# RP2350A_DEV_Template.net
KiCad netlist of a schematic drawn in EAGLE
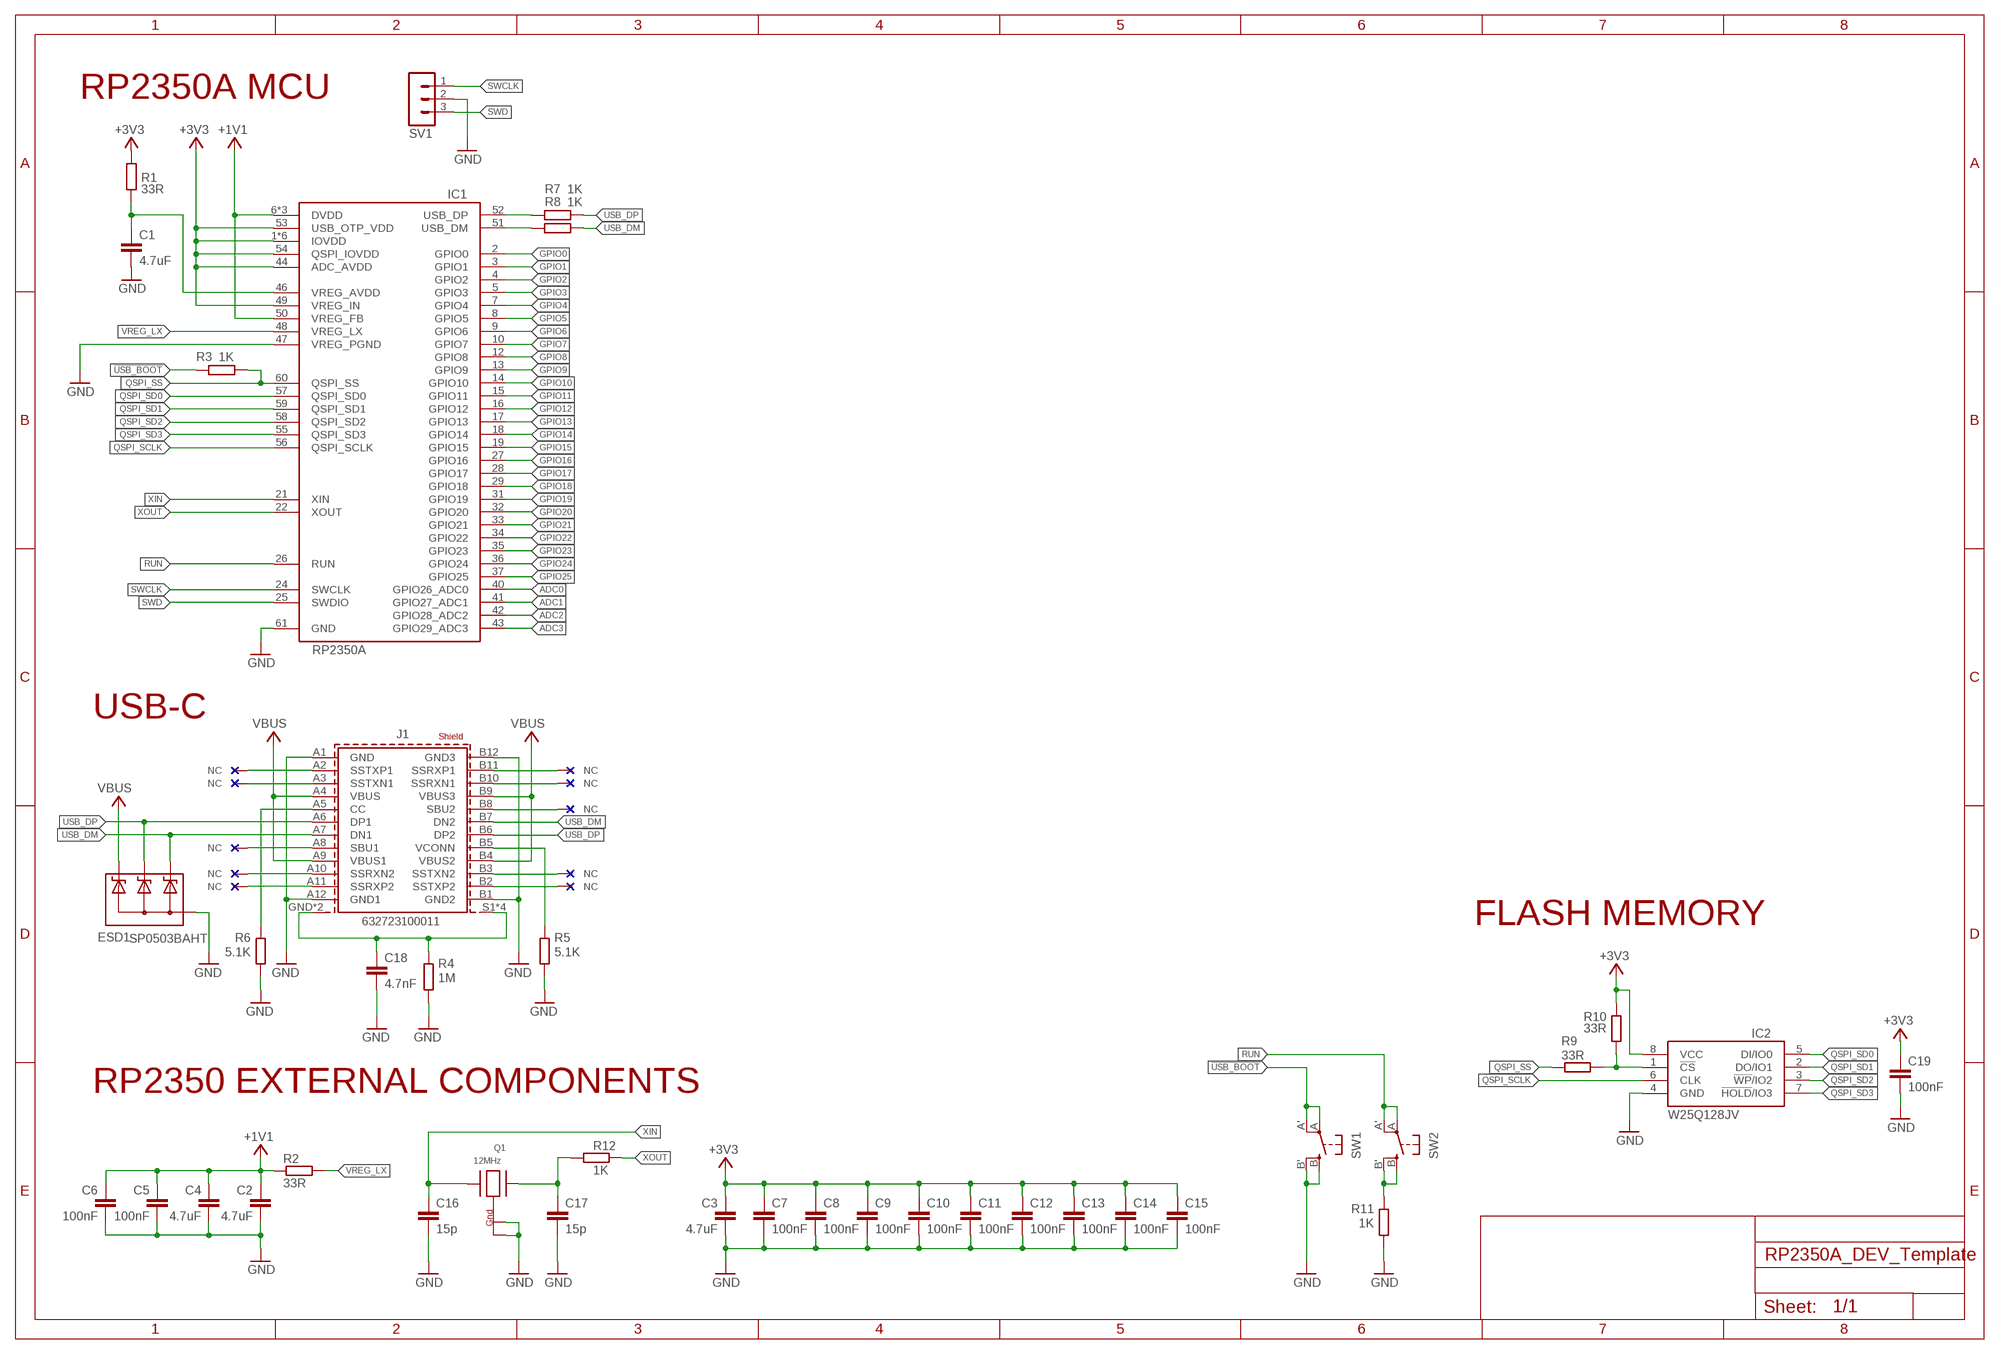
[diagram p0: schematic, sheet 1]

(export (version "E")
  (design (tool "Eeschema 10.0.6"))
  (components
    (comp (ref "C1")
      (value "4.7uF")
      (footprint "eagle-import:C0402K")
      (libsource (lib "eagle-import") (part "C-EUC0402K"))
    )
    (comp (ref "C2")
      (value "4.7uF")
      (footprint "eagle-import:C0402K")
      (libsource (lib "eagle-import") (part "C-EUC0402K"))
    )
    (comp (ref "C3")
      (value "4.7uF")
      (footprint "eagle-import:C0402K")
      (libsource (lib "eagle-import") (part "C-EUC0402K"))
    )
    (comp (ref "C4")
      (value "4.7uF")
      (footprint "eagle-import:C0402K")
      (libsource (lib "eagle-import") (part "C-EUC0402K"))
    )
    (comp (ref "C5")
      (value "100nF")
      (footprint "eagle-import:C0402K")
      (libsource (lib "eagle-import") (part "C-EUC0402K"))
    )
    (comp (ref "C6")
      (value "100nF")
      (footprint "eagle-import:C0402K")
      (libsource (lib "eagle-import") (part "C-EUC0402K"))
    )
    (comp (ref "C7")
      (value "100nF")
      (footprint "eagle-import:C0402K")
      (libsource (lib "eagle-import") (part "C-EUC0402K"))
    )
    (comp (ref "C8")
      (value "100nF")
      (footprint "eagle-import:C0402K")
      (libsource (lib "eagle-import") (part "C-EUC0402K"))
    )
    (comp (ref "C9")
      (value "100nF")
      (footprint "eagle-import:C0402K")
      (libsource (lib "eagle-import") (part "C-EUC0402K"))
    )
    (comp (ref "C10")
      (value "100nF")
      (footprint "eagle-import:C0402K")
      (libsource (lib "eagle-import") (part "C-EUC0402K"))
    )
    (comp (ref "C11")
      (value "100nF")
      (footprint "eagle-import:C0402K")
      (libsource (lib "eagle-import") (part "C-EUC0402K"))
    )
    (comp (ref "C12")
      (value "100nF")
      (footprint "eagle-import:C0402K")
      (libsource (lib "eagle-import") (part "C-EUC0402K"))
    )
    (comp (ref "C13")
      (value "100nF")
      (footprint "eagle-import:C0402K")
      (libsource (lib "eagle-import") (part "C-EUC0402K"))
    )
    (comp (ref "C14")
      (value "100nF")
      (footprint "eagle-import:C0402K")
      (libsource (lib "eagle-import") (part "C-EUC0402K"))
    )
    (comp (ref "C15")
      (value "100nF")
      (footprint "eagle-import:C0402K")
      (libsource (lib "eagle-import") (part "C-EUC0402K"))
    )
    (comp (ref "C16")
      (value "15p")
      (footprint "eagle-import:C0402K")
      (libsource (lib "eagle-import") (part "C-EUC0402K"))
    )
    (comp (ref "C17")
      (value "15p")
      (footprint "eagle-import:C0402K")
      (libsource (lib "eagle-import") (part "C-EUC0402K"))
    )
    (comp (ref "C18")
      (value "4.7nF")
      (footprint "eagle-import:C0402K")
      (libsource (lib "eagle-import") (part "C-EUC0402K"))
    )
    (comp (ref "C19")
      (value "100nF")
      (footprint "eagle-import:C0402K")
      (libsource (lib "eagle-import") (part "C-EUC0402K"))
    )
    (comp (ref "ESD1")
      (value "SP0503BAHT")
      (footprint "eagle-import:SOT143")
      (libsource (lib "eagle-import") (part "SP0503BAHT"))
    )
    (comp (ref "IC1")
      (value "RP2350AA")
      (footprint "eagle-import:QFN40P700X700X85-61T340N")
      (libsource (lib "eagle-import") (part "RP2350AA"))
    )
    (comp (ref "IC2")
      (value "W25Q128JVP")
      (footprint "eagle-import:SON127P600X500X75-8N")
      (libsource (lib "eagle-import") (part "W25Q128JVP"))
    )
    (comp (ref "J1")
      (value "632723100011")
      (footprint "eagle-import:632723100011")
      (libsource (lib "eagle-import") (part "632723100011"))
    )
    (comp (ref "Q1")
      (value "12MHz")
      (footprint "eagle-import:NX3225")
      (libsource (lib "eagle-import") (part "XTAL-4-3225"))
    )
    (comp (ref "R1")
      (value "33R")
      (footprint "eagle-import:R0402")
      (libsource (lib "eagle-import") (part "R-EU_R0402"))
    )
    (comp (ref "R2")
      (value "33R")
      (footprint "eagle-import:R0402")
      (libsource (lib "eagle-import") (part "R-EU_R0402"))
    )
    (comp (ref "R3")
      (value "1K")
      (footprint "eagle-import:R0402")
      (libsource (lib "eagle-import") (part "R-EU_R0402"))
    )
    (comp (ref "R4")
      (value "1M")
      (footprint "eagle-import:R0402")
      (libsource (lib "eagle-import") (part "R-EU_R0402"))
    )
    (comp (ref "R5")
      (value "5.1K")
      (footprint "eagle-import:R0402")
      (libsource (lib "eagle-import") (part "R-EU_R0402"))
    )
    (comp (ref "R6")
      (value "5.1K")
      (footprint "eagle-import:R0402")
      (libsource (lib "eagle-import") (part "R-EU_R0402"))
    )
    (comp (ref "R7")
      (value "1K")
      (footprint "eagle-import:R0402")
      (libsource (lib "eagle-import") (part "R-EU_R0402"))
    )
    (comp (ref "R8")
      (value "1K")
      (footprint "eagle-import:R0402")
      (libsource (lib "eagle-import") (part "R-EU_R0402"))
    )
    (comp (ref "R9")
      (value "33R")
      (footprint "eagle-import:R0402")
      (libsource (lib "eagle-import") (part "R-EU_R0402"))
    )
    (comp (ref "R10")
      (value "33R")
      (footprint "eagle-import:R0402")
      (libsource (lib "eagle-import") (part "R-EU_R0402"))
    )
    (comp (ref "R11")
      (value "1K")
      (footprint "eagle-import:R0402")
      (libsource (lib "eagle-import") (part "R-EU_R0402"))
    )
    (comp (ref "R12")
      (value "1K")
      (footprint "eagle-import:R0402")
      (libsource (lib "eagle-import") (part "R-EU_R0402"))
    )
    (comp (ref "SV1")
      (value "MA03-1")
      (footprint "eagle-import:MA03-1")
      (libsource (lib "eagle-import") (part "MA03-1"))
    )
    (comp (ref "SW1")
      (value "SPST_TACT-EVQQ2")
      (footprint "eagle-import:EVQ-Q2")
      (libsource (lib "eagle-import") (part "SPST_TACT-EVQQ2"))
    )
    (comp (ref "SW2")
      (value "SPST_TACT-EVQQ2")
      (footprint "eagle-import:EVQ-Q2")
      (libsource (lib "eagle-import") (part "SPST_TACT-EVQQ2"))
    )
  )
  (nets
    (net (code "1") (name "+1V1") (class "Default")
      (node (ref "C2") (pin "1") (pinfunction "1_1") (pintype "passive"))
      (node (ref "C4") (pin "1") (pinfunction "1_1") (pintype "passive"))
      (node (ref "C5") (pin "1") (pinfunction "1_1") (pintype "passive"))
      (node (ref "C6") (pin "1") (pinfunction "1_1") (pintype "passive"))
      (node (ref "IC1") (pin "23") (pinfunction "DVDD_23") (pintype "power_in"))
      (node (ref "IC1") (pin "39") (pinfunction "DVDD_39") (pintype "power_in"))
      (node (ref "IC1") (pin "50") (pinfunction "VREG_FB_50") (pintype "power_in"))
      (node (ref "IC1") (pin "6") (pinfunction "DVDD_6") (pintype "power_in"))
      (node (ref "R2") (pin "2") (pinfunction "2_2") (pintype "passive"))
    )
    (net (code "2") (name "+3V3") (class "Default")
      (node (ref "C10") (pin "1") (pinfunction "1_1") (pintype "passive"))
      (node (ref "C11") (pin "1") (pinfunction "1_1") (pintype "passive"))
      (node (ref "C12") (pin "1") (pinfunction "1_1") (pintype "passive"))
      (node (ref "C13") (pin "1") (pinfunction "1_1") (pintype "passive"))
      (node (ref "C14") (pin "1") (pinfunction "1_1") (pintype "passive"))
      (node (ref "C15") (pin "1") (pinfunction "1_1") (pintype "passive"))
      (node (ref "C19") (pin "1") (pinfunction "1_1") (pintype "passive"))
      (node (ref "C3") (pin "1") (pinfunction "1_1") (pintype "passive"))
      (node (ref "C7") (pin "1") (pinfunction "1_1") (pintype "passive"))
      (node (ref "C8") (pin "1") (pinfunction "1_1") (pintype "passive"))
      (node (ref "C9") (pin "1") (pinfunction "1_1") (pintype "passive"))
      (node (ref "IC1") (pin "1") (pinfunction "IOVDD_1") (pintype "power_in"))
      (node (ref "IC1") (pin "11") (pinfunction "IOVDD_11") (pintype "power_in"))
      (node (ref "IC1") (pin "20") (pinfunction "IOVDD_20") (pintype "power_in"))
      (node (ref "IC1") (pin "30") (pinfunction "IOVDD_30") (pintype "power_in"))
      (node (ref "IC1") (pin "38") (pinfunction "IOVDD_38") (pintype "power_in"))
      (node (ref "IC1") (pin "44") (pinfunction "ADC_AVDD_44") (pintype "power_in"))
      (node (ref "IC1") (pin "45") (pinfunction "IOVDD_45") (pintype "power_in"))
      (node (ref "IC1") (pin "49") (pinfunction "VREG_IN_49") (pintype "power_in"))
      (node (ref "IC1") (pin "53") (pinfunction "USB_OTP_VDD_53") (pintype "bidirectional"))
      (node (ref "IC1") (pin "54") (pinfunction "QSPI_IOVDD_54") (pintype "power_in"))
      (node (ref "IC2") (pin "8") (pinfunction "VCC_8") (pintype "power_in"))
      (node (ref "R1") (pin "1") (pinfunction "1_1") (pintype "passive"))
      (node (ref "R10") (pin "1") (pinfunction "1_1") (pintype "passive"))
    )
    (net (code "3") (name "/~{USB_BOOT}") (class "Default")
      (node (ref "R3") (pin "1") (pinfunction "1_1") (pintype "passive"))
      (node (ref "SW1") (pin "A") (pinfunction "P_A") (pintype "passive"))
      (node (ref "SW1") (pin "A'") (pinfunction "P1_A'") (pintype "passive"))
    )
    (net (code "4") (name "ADC0") (class "Default")
      (node (ref "IC1") (pin "40") (pinfunction "GPIO26_ADC0_40") (pintype "bidirectional"))
    )
    (net (code "5") (name "ADC1") (class "Default")
      (node (ref "IC1") (pin "41") (pinfunction "GPIO27_ADC1_41") (pintype "bidirectional"))
    )
    (net (code "6") (name "ADC2") (class "Default")
      (node (ref "IC1") (pin "42") (pinfunction "GPIO28_ADC2_42") (pintype "bidirectional"))
    )
    (net (code "7") (name "ADC3") (class "Default")
      (node (ref "IC1") (pin "43") (pinfunction "GPIO29_ADC3_43") (pintype "bidirectional"))
    )
    (net (code "8") (name "GND") (class "Default")
      (node (ref "C1") (pin "2") (pinfunction "2_2") (pintype "passive"))
      (node (ref "C10") (pin "2") (pinfunction "2_2") (pintype "passive"))
      (node (ref "C11") (pin "2") (pinfunction "2_2") (pintype "passive"))
      (node (ref "C12") (pin "2") (pinfunction "2_2") (pintype "passive"))
      (node (ref "C13") (pin "2") (pinfunction "2_2") (pintype "passive"))
      (node (ref "C14") (pin "2") (pinfunction "2_2") (pintype "passive"))
      (node (ref "C15") (pin "2") (pinfunction "2_2") (pintype "passive"))
      (node (ref "C16") (pin "2") (pinfunction "2_2") (pintype "passive"))
      (node (ref "C17") (pin "2") (pinfunction "2_2") (pintype "passive"))
      (node (ref "C18") (pin "2") (pinfunction "2_2") (pintype "passive"))
      (node (ref "C19") (pin "2") (pinfunction "2_2") (pintype "passive"))
      (node (ref "C2") (pin "2") (pinfunction "2_2") (pintype "passive"))
      (node (ref "C3") (pin "2") (pinfunction "2_2") (pintype "passive"))
      (node (ref "C4") (pin "2") (pinfunction "2_2") (pintype "passive"))
      (node (ref "C5") (pin "2") (pinfunction "2_2") (pintype "passive"))
      (node (ref "C6") (pin "2") (pinfunction "2_2") (pintype "passive"))
      (node (ref "C7") (pin "2") (pinfunction "2_2") (pintype "passive"))
      (node (ref "C8") (pin "2") (pinfunction "2_2") (pintype "passive"))
      (node (ref "C9") (pin "2") (pinfunction "2_2") (pintype "passive"))
      (node (ref "ESD1") (pin "1") (pinfunction "A_1") (pintype "bidirectional"))
      (node (ref "IC1") (pin "47") (pinfunction "VREG_PGND_47") (pintype "power_in"))
      (node (ref "IC1") (pin "61") (pinfunction "GND_61") (pintype "power_in"))
      (node (ref "IC2") (pin "4") (pinfunction "GND_4") (pintype "power_in"))
      (node (ref "J1") (pin "A1") (pinfunction "GND_A1") (pintype "passive"))
      (node (ref "J1") (pin "A12") (pinfunction "GND1_A12") (pintype "passive"))
      (node (ref "J1") (pin "B1") (pinfunction "GND2_B1") (pintype "passive"))
      (node (ref "J1") (pin "B12") (pinfunction "GND3_B12") (pintype "passive"))
      (node (ref "Q1") (pin "2") (pinfunction "G2_2") (pintype "power_in"))
      (node (ref "Q1") (pin "4") (pinfunction "G1_4") (pintype "power_in"))
      (node (ref "R11") (pin "1") (pinfunction "1_1") (pintype "passive"))
      (node (ref "R4") (pin "1") (pinfunction "1_1") (pintype "passive"))
      (node (ref "R5") (pin "1") (pinfunction "1_1") (pintype "passive"))
      (node (ref "R6") (pin "1") (pinfunction "1_1") (pintype "passive"))
      (node (ref "SV1") (pin "2") (pinfunction "2_2") (pintype "passive"))
      (node (ref "SW1") (pin "B") (pinfunction "S_B") (pintype "passive"))
      (node (ref "SW1") (pin "B'") (pinfunction "S1_B'") (pintype "passive"))
    )
    (net (code "9") (name "GPIO0") (class "Default")
      (node (ref "IC1") (pin "2") (pinfunction "GPIO0_2") (pintype "bidirectional"))
    )
    (net (code "10") (name "GPIO1") (class "Default")
      (node (ref "IC1") (pin "3") (pinfunction "GPIO1_3") (pintype "bidirectional"))
    )
    (net (code "11") (name "GPIO2") (class "Default")
      (node (ref "IC1") (pin "4") (pinfunction "GPIO2_4") (pintype "bidirectional"))
    )
    (net (code "12") (name "GPIO3") (class "Default")
      (node (ref "IC1") (pin "5") (pinfunction "GPIO3_5") (pintype "bidirectional"))
    )
    (net (code "13") (name "GPIO4") (class "Default")
      (node (ref "IC1") (pin "7") (pinfunction "GPIO4_7") (pintype "bidirectional"))
    )
    (net (code "14") (name "GPIO5") (class "Default")
      (node (ref "IC1") (pin "8") (pinfunction "GPIO5_8") (pintype "bidirectional"))
    )
    (net (code "15") (name "GPIO6") (class "Default")
      (node (ref "IC1") (pin "9") (pinfunction "GPIO6_9") (pintype "bidirectional"))
    )
    (net (code "16") (name "GPIO7") (class "Default")
      (node (ref "IC1") (pin "10") (pinfunction "GPIO7_10") (pintype "bidirectional"))
    )
    (net (code "17") (name "GPIO8") (class "Default")
      (node (ref "IC1") (pin "12") (pinfunction "GPIO8_12") (pintype "bidirectional"))
    )
    (net (code "18") (name "GPIO9") (class "Default")
      (node (ref "IC1") (pin "13") (pinfunction "GPIO9_13") (pintype "bidirectional"))
    )
    (net (code "19") (name "GPIO10") (class "Default")
      (node (ref "IC1") (pin "14") (pinfunction "GPIO10_14") (pintype "bidirectional"))
    )
    (net (code "20") (name "GPIO11") (class "Default")
      (node (ref "IC1") (pin "15") (pinfunction "GPIO11_15") (pintype "bidirectional"))
    )
    (net (code "21") (name "GPIO12") (class "Default")
      (node (ref "IC1") (pin "16") (pinfunction "GPIO12_16") (pintype "bidirectional"))
    )
    (net (code "22") (name "GPIO13") (class "Default")
      (node (ref "IC1") (pin "17") (pinfunction "GPIO13_17") (pintype "bidirectional"))
    )
    (net (code "23") (name "GPIO14") (class "Default")
      (node (ref "IC1") (pin "18") (pinfunction "GPIO14_18") (pintype "bidirectional"))
    )
    (net (code "24") (name "GPIO15") (class "Default")
      (node (ref "IC1") (pin "19") (pinfunction "GPIO15_19") (pintype "bidirectional"))
    )
    (net (code "25") (name "GPIO16") (class "Default")
      (node (ref "IC1") (pin "27") (pinfunction "GPIO16_27") (pintype "bidirectional"))
    )
    (net (code "26") (name "GPIO17") (class "Default")
      (node (ref "IC1") (pin "28") (pinfunction "GPIO17_28") (pintype "bidirectional"))
    )
    (net (code "27") (name "GPIO18") (class "Default")
      (node (ref "IC1") (pin "29") (pinfunction "GPIO18_29") (pintype "bidirectional"))
    )
    (net (code "28") (name "GPIO19") (class "Default")
      (node (ref "IC1") (pin "31") (pinfunction "GPIO19_31") (pintype "bidirectional"))
    )
    (net (code "29") (name "GPIO20") (class "Default")
      (node (ref "IC1") (pin "32") (pinfunction "GPIO20_32") (pintype "bidirectional"))
    )
    (net (code "30") (name "GPIO21") (class "Default")
      (node (ref "IC1") (pin "33") (pinfunction "GPIO21_33") (pintype "bidirectional"))
    )
    (net (code "31") (name "GPIO22") (class "Default")
      (node (ref "IC1") (pin "34") (pinfunction "GPIO22_34") (pintype "bidirectional"))
    )
    (net (code "32") (name "GPIO23") (class "Default")
      (node (ref "IC1") (pin "35") (pinfunction "GPIO23_35") (pintype "bidirectional"))
    )
    (net (code "33") (name "GPIO24") (class "Default")
      (node (ref "IC1") (pin "36") (pinfunction "GPIO24_36") (pintype "bidirectional"))
    )
    (net (code "34") (name "GPIO25") (class "Default")
      (node (ref "IC1") (pin "37") (pinfunction "GPIO25_37") (pintype "bidirectional"))
    )
    (net (code "35") (name "Net-(C18-Pad1)") (class "Default")
      (node (ref "C18") (pin "1") (pinfunction "1_1") (pintype "passive"))
      (node (ref "J1") (pin "GND") (pinfunction "SHIELD_GND") (pintype "passive"))
      (node (ref "J1") (pin "GND1") (pinfunction "SHIELD_GND1") (pintype "passive"))
      (node (ref "J1") (pin "S1") (pinfunction "SHIELD1_S1") (pintype "passive"))
      (node (ref "J1") (pin "S2") (pinfunction "SHIELD1_S2") (pintype "passive"))
      (node (ref "J1") (pin "S3") (pinfunction "SHIELD1_S3") (pintype "passive"))
      (node (ref "J1") (pin "S4") (pinfunction "SHIELD1_S4") (pintype "passive"))
      (node (ref "R4") (pin "2") (pinfunction "2_2") (pintype "passive"))
    )
    (net (code "36") (name "Net-(IC1-USB_DM)") (class "Default")
      (node (ref "IC1") (pin "51") (pinfunction "USB_DM_51") (pintype "bidirectional"))
      (node (ref "R8") (pin "1") (pinfunction "1_1") (pintype "passive"))
    )
    (net (code "37") (name "Net-(IC1-USB_DP)") (class "Default")
      (node (ref "IC1") (pin "52") (pinfunction "USB_DP_52") (pintype "bidirectional"))
      (node (ref "R7") (pin "1") (pinfunction "1_1") (pintype "passive"))
    )
    (net (code "38") (name "Net-(IC1-VREG_AVDD)") (class "Default")
      (node (ref "C1") (pin "1") (pinfunction "1_1") (pintype "passive"))
      (node (ref "IC1") (pin "46") (pinfunction "VREG_AVDD_46") (pintype "power_in"))
      (node (ref "R1") (pin "2") (pinfunction "2_2") (pintype "passive"))
    )
    (net (code "39") (name "Net-(IC2-~{CS})") (class "Default")
      (node (ref "IC2") (pin "1") (pinfunction "~{CS}_1") (pintype "bidirectional"))
      (node (ref "R10") (pin "2") (pinfunction "2_2") (pintype "passive"))
      (node (ref "R9") (pin "2") (pinfunction "2_2") (pintype "passive"))
    )
    (net (code "40") (name "Net-(J1-CC)") (class "Default")
      (node (ref "J1") (pin "A5") (pinfunction "CC_A5") (pintype "passive"))
      (node (ref "R6") (pin "2") (pinfunction "2_2") (pintype "passive"))
    )
    (net (code "41") (name "Net-(J1-VCONN)") (class "Default")
      (node (ref "J1") (pin "B5") (pinfunction "VCONN_B5") (pintype "passive"))
      (node (ref "R5") (pin "2") (pinfunction "2_2") (pintype "passive"))
    )
    (net (code "42") (name "Net-(Q1-X1)") (class "Default")
      (node (ref "C17") (pin "1") (pinfunction "1_1") (pintype "passive"))
      (node (ref "Q1") (pin "1") (pinfunction "X1_1") (pintype "bidirectional"))
      (node (ref "R12") (pin "1") (pinfunction "1_1") (pintype "passive"))
    )
    (net (code "43") (name "Net-(SW2-S)") (class "Default")
      (node (ref "R11") (pin "2") (pinfunction "2_2") (pintype "passive"))
      (node (ref "SW2") (pin "B") (pinfunction "S_B") (pintype "passive"))
      (node (ref "SW2") (pin "B'") (pinfunction "S1_B'") (pintype "passive"))
    )
    (net (code "44") (name "QSPI_SCLK") (class "Default")
      (node (ref "IC1") (pin "56") (pinfunction "QSPI_SCLK_56") (pintype "bidirectional"))
      (node (ref "IC2") (pin "6") (pinfunction "CLK_6") (pintype "bidirectional"))
    )
    (net (code "45") (name "QSPI_SD0") (class "Default")
      (node (ref "IC1") (pin "57") (pinfunction "QSPI_SD0_57") (pintype "bidirectional"))
      (node (ref "IC2") (pin "5") (pinfunction "DI/IO0_5") (pintype "bidirectional"))
    )
    (net (code "46") (name "QSPI_SD1") (class "Default")
      (node (ref "IC1") (pin "59") (pinfunction "QSPI_SD1_59") (pintype "bidirectional"))
      (node (ref "IC2") (pin "2") (pinfunction "DO/IO1_2") (pintype "bidirectional"))
    )
    (net (code "47") (name "QSPI_SD2") (class "Default")
      (node (ref "IC1") (pin "58") (pinfunction "QSPI_SD2_58") (pintype "bidirectional"))
      (node (ref "IC2") (pin "3") (pinfunction "~{WP}/IO2_3") (pintype "bidirectional"))
    )
    (net (code "48") (name "QSPI_SD3") (class "Default")
      (node (ref "IC1") (pin "55") (pinfunction "QSPI_SD3_55") (pintype "bidirectional"))
      (node (ref "IC2") (pin "7") (pinfunction "~{HOLD}/IO3_7") (pintype "bidirectional"))
    )
    (net (code "49") (name "QSPI_SS") (class "Default")
      (node (ref "IC1") (pin "60") (pinfunction "QSPI_SS_60") (pintype "bidirectional"))
      (node (ref "R3") (pin "2") (pinfunction "2_2") (pintype "passive"))
      (node (ref "R9") (pin "1") (pinfunction "1_1") (pintype "passive"))
    )
    (net (code "50") (name "RUN") (class "Default")
      (node (ref "IC1") (pin "26") (pinfunction "RUN_26") (pintype "bidirectional"))
      (node (ref "SW2") (pin "A") (pinfunction "P_A") (pintype "passive"))
      (node (ref "SW2") (pin "A'") (pinfunction "P1_A'") (pintype "passive"))
    )
    (net (code "51") (name "SWCLK") (class "Default")
      (node (ref "IC1") (pin "24") (pinfunction "SWCLK_24") (pintype "bidirectional"))
      (node (ref "SV1") (pin "1") (pinfunction "1_1") (pintype "passive"))
    )
    (net (code "52") (name "SWD") (class "Default")
      (node (ref "IC1") (pin "25") (pinfunction "SWDIO_25") (pintype "bidirectional"))
      (node (ref "SV1") (pin "3") (pinfunction "3_3") (pintype "passive"))
    )
    (net (code "53") (name "USB_DM") (class "Default")
      (node (ref "ESD1") (pin "2") (pinfunction "C1_2") (pintype "bidirectional"))
      (node (ref "J1") (pin "A7") (pinfunction "DN1_A7") (pintype "passive"))
      (node (ref "J1") (pin "B7") (pinfunction "DN2_B7") (pintype "passive"))
      (node (ref "R8") (pin "2") (pinfunction "2_2") (pintype "passive"))
    )
    (net (code "54") (name "USB_DP") (class "Default")
      (node (ref "ESD1") (pin "3") (pinfunction "C2_3") (pintype "bidirectional"))
      (node (ref "J1") (pin "A6") (pinfunction "DP1_A6") (pintype "passive"))
      (node (ref "J1") (pin "B6") (pinfunction "DP2_B6") (pintype "passive"))
      (node (ref "R7") (pin "2") (pinfunction "2_2") (pintype "passive"))
    )
    (net (code "55") (name "VBUS") (class "Default")
      (node (ref "ESD1") (pin "4") (pinfunction "C3_4") (pintype "bidirectional"))
      (node (ref "J1") (pin "A4") (pinfunction "VBUS_A4") (pintype "passive"))
      (node (ref "J1") (pin "A9") (pinfunction "VBUS1_A9") (pintype "passive"))
      (node (ref "J1") (pin "B4") (pinfunction "VBUS2_B4") (pintype "passive"))
      (node (ref "J1") (pin "B9") (pinfunction "VBUS3_B9") (pintype "passive"))
    )
    (net (code "56") (name "VREG_LX") (class "Default")
      (node (ref "IC1") (pin "48") (pinfunction "VREG_LX_48") (pintype "power_in"))
      (node (ref "R2") (pin "1") (pinfunction "1_1") (pintype "passive"))
    )
    (net (code "57") (name "XIN") (class "Default")
      (node (ref "C16") (pin "1") (pinfunction "1_1") (pintype "passive"))
      (node (ref "IC1") (pin "21") (pinfunction "XIN_21") (pintype "input"))
      (node (ref "Q1") (pin "3") (pinfunction "X2_3") (pintype "bidirectional"))
    )
    (net (code "58") (name "XOUT") (class "Default")
      (node (ref "IC1") (pin "22") (pinfunction "XOUT_22") (pintype "output"))
      (node (ref "R12") (pin "2") (pinfunction "2_2") (pintype "passive"))
    )
    (net (code "59") (name "unconnected-(J1-SBU1-PadA8)") (class "Default")
      (node (ref "J1") (pin "A8") (pinfunction "SBU1_A8") (pintype "passive"))
    )
    (net (code "60") (name "unconnected-(J1-SBU2-PadB8)") (class "Default")
      (node (ref "J1") (pin "B8") (pinfunction "SBU2_B8") (pintype "passive"))
    )
    (net (code "61") (name "unconnected-(J1-SSRXN1-PadB10)") (class "Default")
      (node (ref "J1") (pin "B10") (pinfunction "SSRXN1_B10") (pintype "passive"))
    )
    (net (code "62") (name "unconnected-(J1-SSRXN2-PadA10)") (class "Default")
      (node (ref "J1") (pin "A10") (pinfunction "SSRXN2_A10") (pintype "passive"))
    )
    (net (code "63") (name "unconnected-(J1-SSRXP1-PadB11)") (class "Default")
      (node (ref "J1") (pin "B11") (pinfunction "SSRXP1_B11") (pintype "passive"))
    )
    (net (code "64") (name "unconnected-(J1-SSRXP2-PadA11)") (class "Default")
      (node (ref "J1") (pin "A11") (pinfunction "SSRXP2_A11") (pintype "passive"))
    )
    (net (code "65") (name "unconnected-(J1-SSTXN1-PadA3)") (class "Default")
      (node (ref "J1") (pin "A3") (pinfunction "SSTXN1_A3") (pintype "passive"))
    )
    (net (code "66") (name "unconnected-(J1-SSTXN2-PadB3)") (class "Default")
      (node (ref "J1") (pin "B3") (pinfunction "SSTXN2_B3") (pintype "passive"))
    )
    (net (code "67") (name "unconnected-(J1-SSTXP1-PadA2)") (class "Default")
      (node (ref "J1") (pin "A2") (pinfunction "SSTXP1_A2") (pintype "passive"))
    )
    (net (code "68") (name "unconnected-(J1-SSTXP2-PadB2)") (class "Default")
      (node (ref "J1") (pin "B2") (pinfunction "SSTXP2_B2") (pintype "passive"))
    )
  )
)
